# a2c.net
KiCad netlist of a schematic drawn in Altium Designer
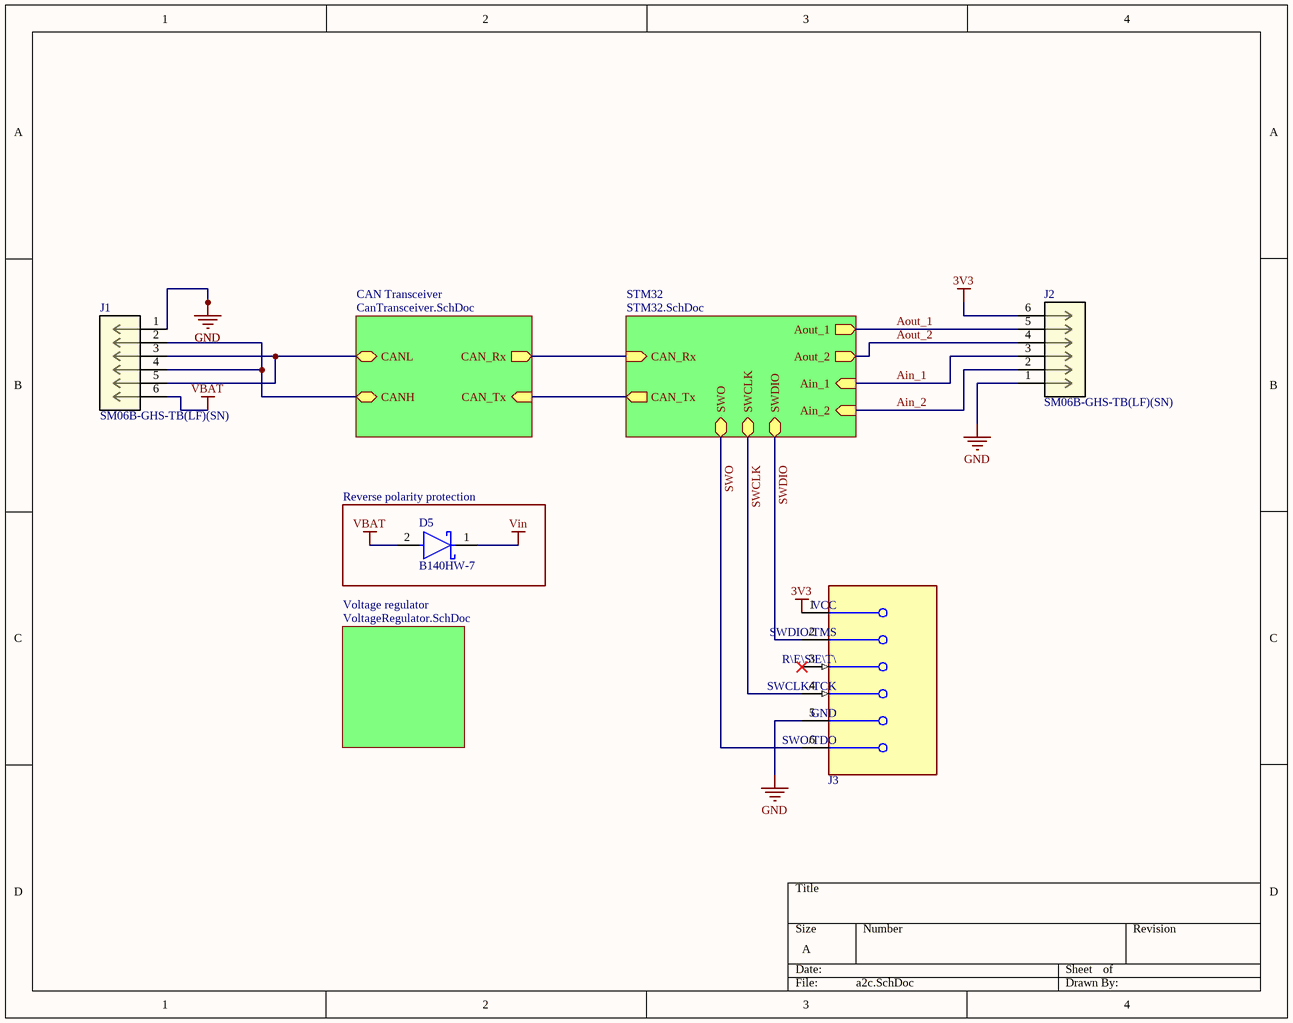
[diagram p0: a2c.SchDoc]

(export (version "E")
  (design (tool "Eeschema 10.0.6"))
  (components
    (comp (ref "D5")
      (value "B140HW-7")
      (footprint "FP-SOD123-MFG")
      (description "DIODE SCHOTTKY 40V 1A SOD123")
      (fields
        (field (name "MANUFACTURER") "Diodes Inc.")
        (field (name "OCTOPART") "https://octopart.com/b140hw-7-diodes+inc.-325751")
      )
      (libsource (lib "Altium Content Vault") (part "1d6ec82d83fb6aee721767c19dac4b9"))
    )
    (comp (ref "J1")
      (value "SM06B-GHS-TB(LF)(SN)")
      (footprint "CONN_SM06B-GHS-TB_JST")
      (description "No Description Available")
      (fields
        (field (name "OCTOPART") "https://octopart.com/b6b-zr-sm4-tf%28lf%29%28sn%29-jst-248849")
        (field (name "MANUFACTURER") "JST")
        (field (name "COPYRIGHT") "Copyright (C) 2021 Ultra Librarian. All rights reserved.")
      )
      (libsource (lib "SM06B-GHS-TB_LF__SN_") (part "SM06B-GHS-TB(LF)(SN)"))
    )
    (comp (ref "J2")
      (value "SM06B-GHS-TB(LF)(SN)")
      (footprint "CONN_SM06B-GHS-TB_JST")
      (description "No Description Available")
      (fields
        (field (name "OCTOPART") "https://octopart.com/b6b-zr-sm4-tf%28lf%29%28sn%29-jst-248849")
        (field (name "MANUFACTURER") "JST")
        (field (name "COPYRIGHT") "Copyright (C) 2021 Ultra Librarian. All rights reserved.")
      )
      (libsource (lib "") (part "SM06B-GHS-TB(LF)(SN)_1"))
    )
    (comp (ref "J3")
      (value "TC2030-CTX-NL")
      (footprint "Tag_Connect_0_MFG")
      (libsource (lib "Conn_Tag_Connect_TC2030-CTX-NL_eec") (part "TC2030-CTX-NL"))
    )
  )
  (nets
    (net (code "1") (name "/Ain_1") (class "Default")
      (node (ref "J2") (pin "3") (pinfunction "3_3") (pintype "passive"))
    )
    (net (code "2") (name "/Ain_2") (class "Default")
      (node (ref "J2") (pin "2") (pinfunction "2_2") (pintype "passive"))
    )
    (net (code "3") (name "/Aout_1") (class "Default")
      (node (ref "J2") (pin "5") (pinfunction "5_5") (pintype "passive"))
    )
    (net (code "4") (name "/Aout_2") (class "Default")
      (node (ref "J2") (pin "4") (pinfunction "4_4") (pintype "passive"))
    )
    (net (code "5") (name "/CANH") (class "Default")
      (node (ref "J1") (pin "2") (pinfunction "2_2") (pintype "passive"))
      (node (ref "J1") (pin "4") (pinfunction "4_4") (pintype "passive"))
    )
    (net (code "6") (name "/CANL") (class "Default")
      (node (ref "J1") (pin "3") (pinfunction "3_3") (pintype "passive"))
      (node (ref "J1") (pin "5") (pinfunction "5_5") (pintype "passive"))
    )
    (net (code "9") (name "/SWCLK") (class "Default")
      (node (ref "J3") (pin "4") (pinfunction "SWCLK/TCK_4") (pintype "input"))
    )
    (net (code "10") (name "/SWDIO") (class "Default")
      (node (ref "J3") (pin "2") (pinfunction "SWDIO/TMS_2") (pintype "passive"))
    )
    (net (code "11") (name "/SWO") (class "Default")
      (node (ref "J3") (pin "6") (pinfunction "SWO/TDO_6") (pintype "passive"))
    )
    (net (code "12") (name "3V3") (class "Default")
      (node (ref "J2") (pin "6") (pinfunction "6_6") (pintype "passive"))
      (node (ref "J3") (pin "1") (pinfunction "VCC_1") (pintype "power_in"))
    )
    (net (code "13") (name "GND") (class "Default")
      (node (ref "J1") (pin "1") (pinfunction "1_1") (pintype "passive"))
      (node (ref "J2") (pin "1") (pinfunction "1_1") (pintype "passive"))
      (node (ref "J3") (pin "5") (pinfunction "GND_5") (pintype "power_in"))
    )
    (net (code "14") (name "VBAT") (class "Default")
      (node (ref "D5") (pin "2") (pinfunction "A_2") (pintype "passive"))
      (node (ref "J1") (pin "6") (pinfunction "6_6") (pintype "passive"))
    )
    (net (code "15") (name "Vin") (class "Default")
      (node (ref "D5") (pin "1") (pinfunction "C_1") (pintype "passive"))
    )
    (net (code "16") (name "unconnected-(J3-~{RESET}-Pad3)") (class "Default")
      (node (ref "J3") (pin "3") (pinfunction "~{RESET}_3") (pintype "input+no_connect"))
    )
  )
)
